# Roseta_Switches.net
KiCad netlist of a schematic drawn in Altium Designer
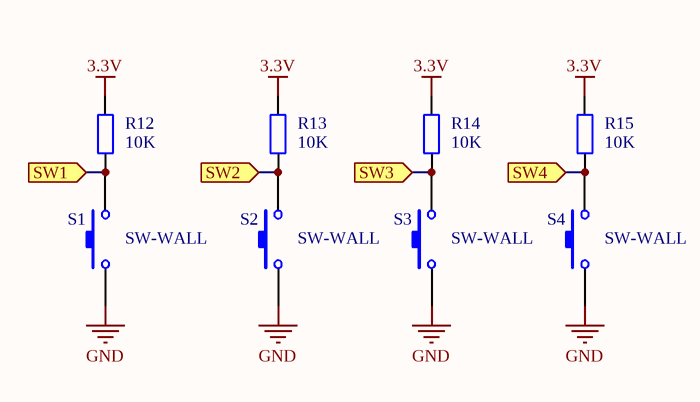
[diagram p0: Roseta_Switches.SchDoc]

(export (version "E")
  (design (tool "Eeschema 10.0.6"))
  (components
    (comp (ref "R12")
      (value "10K")
      (footprint "1608[0603]")
      (description "Resistor")
      (fields (field (name "Comment") "Res2") (field (name "PUBLISHER") "Altium Limited"))
      (libsource (lib "Miscellaneous Devices") (part "Res2"))
    )
    (comp (ref "R13")
      (value "10K")
      (footprint "1608[0603]")
      (description "Resistor")
      (fields (field (name "Comment") "Res2") (field (name "PUBLISHER") "Altium Limited"))
      (libsource (lib "Miscellaneous Devices") (part "Res2"))
    )
    (comp (ref "R14")
      (value "10K")
      (footprint "1608[0603]")
      (description "Resistor")
      (fields (field (name "Comment") "Res2") (field (name "PUBLISHER") "Altium Limited"))
      (libsource (lib "Miscellaneous Devices") (part "Res2"))
    )
    (comp (ref "R15")
      (value "10K")
      (footprint "1608[0603]")
      (description "Resistor")
      (fields (field (name "Comment") "Res2") (field (name "PUBLISHER") "Altium Limited"))
      (libsource (lib "Miscellaneous Devices") (part "Res2"))
    )
    (comp (ref "S1")
      (value "SW-WALL")
      (footprint "TERMINAL BLOCK X2")
      (description "Switch")
      (fields (field (name "PUBLISHER") "Altium Limited"))
      (libsource (lib "Miscellaneous Devices") (part "SW-PB"))
    )
    (comp (ref "S2")
      (value "SW-WALL")
      (footprint "TERMINAL BLOCK X2")
      (description "Switch")
      (fields (field (name "PUBLISHER") "Altium Limited"))
      (libsource (lib "Miscellaneous Devices") (part "SW-PB"))
    )
    (comp (ref "S3")
      (value "SW-WALL")
      (footprint "TERMINAL BLOCK X2")
      (description "Switch")
      (fields (field (name "PUBLISHER") "Altium Limited"))
      (libsource (lib "Miscellaneous Devices") (part "SW-PB"))
    )
    (comp (ref "S4")
      (value "SW-WALL")
      (footprint "TERMINAL BLOCK X2")
      (description "Switch")
      (fields (field (name "PUBLISHER") "Altium Limited"))
      (libsource (lib "Miscellaneous Devices") (part "SW-PB"))
    )
  )
  (nets
    (net (code "1") (name "/SW1") (class "Default")
      (node (ref "R12") (pin "2") (pinfunction "2_2") (pintype "passive"))
      (node (ref "S1") (pin "2") (pinfunction "2_2") (pintype "passive"))
    )
    (net (code "2") (name "/SW2") (class "Default")
      (node (ref "R13") (pin "2") (pinfunction "2_2") (pintype "passive"))
      (node (ref "S2") (pin "2") (pinfunction "2_2") (pintype "passive"))
    )
    (net (code "3") (name "/SW3") (class "Default")
      (node (ref "R14") (pin "2") (pinfunction "2_2") (pintype "passive"))
      (node (ref "S3") (pin "2") (pinfunction "2_2") (pintype "passive"))
    )
    (net (code "4") (name "/SW4") (class "Default")
      (node (ref "R15") (pin "2") (pinfunction "2_2") (pintype "passive"))
      (node (ref "S4") (pin "2") (pinfunction "2_2") (pintype "passive"))
    )
    (net (code "5") (name "3.3V") (class "Default")
      (node (ref "R12") (pin "1") (pinfunction "1_1") (pintype "passive"))
      (node (ref "R13") (pin "1") (pinfunction "1_1") (pintype "passive"))
      (node (ref "R14") (pin "1") (pinfunction "1_1") (pintype "passive"))
      (node (ref "R15") (pin "1") (pinfunction "1_1") (pintype "passive"))
    )
    (net (code "6") (name "GND") (class "Default")
      (node (ref "S1") (pin "1") (pinfunction "1_1") (pintype "passive"))
      (node (ref "S2") (pin "1") (pinfunction "1_1") (pintype "passive"))
      (node (ref "S3") (pin "1") (pinfunction "1_1") (pintype "passive"))
      (node (ref "S4") (pin "1") (pinfunction "1_1") (pintype "passive"))
    )
  )
)
